# BLE_PP_v15.net
KiCad netlist of a schematic drawn in EAGLE
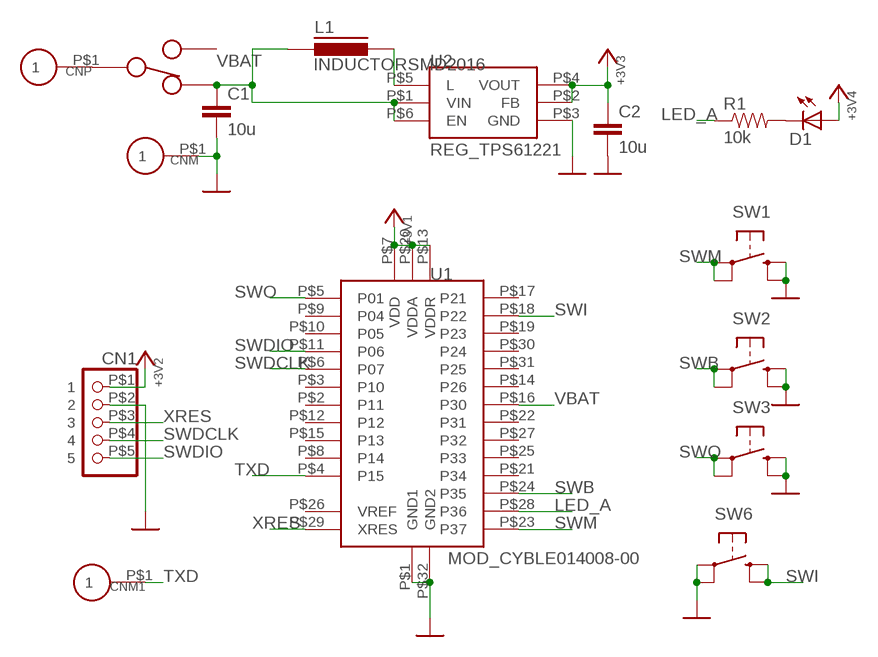
[diagram p0: schematic, sheet 1]

(export (version "E")
  (design (tool "Eeschema 10.0.6"))
  (components
    (comp (ref "C1")
      (value "10u")
      (footprint "eagle-import:0603")
      (libsource (lib "eagle-import") (part "CAP0603"))
    )
    (comp (ref "C2")
      (value "10u")
      (footprint "eagle-import:0603")
      (libsource (lib "eagle-import") (part "CAP0603"))
    )
    (comp (ref "CN1")
      (value "CON_PINHD-1X550MIL")
      (footprint "eagle-import:1X5_50MIL")
      (libsource (lib "eagle-import") (part "CON_PINHD-1X550MIL"))
    )
    (comp (ref "CNM")
      (value "CON_P01SMD1MM")
      (footprint "eagle-import:PAD_SMD1MM")
      (libsource (lib "eagle-import") (part "CON_P01SMD1MM"))
    )
    (comp (ref "CNM1")
      (value "CON_P01SMD1MM")
      (footprint "eagle-import:PAD_SMD1MM")
      (libsource (lib "eagle-import") (part "CON_P01SMD1MM"))
    )
    (comp (ref "CNP")
      (value "CON_P01SMD1MM")
      (footprint "eagle-import:PAD_SMD1MM")
      (libsource (lib "eagle-import") (part "CON_P01SMD1MM"))
    )
    (comp (ref "D1")
      (value "LED0603")
      (footprint "eagle-import:SPARKFUN_LED-0603")
      (libsource (lib "eagle-import") (part "LED0603"))
    )
    (comp (ref "L1")
      (value "INDUCTORSMD2016")
      (footprint "eagle-import:2016")
      (libsource (lib "eagle-import") (part "INDUCTORSMD2016"))
    )
    (comp (ref "R1")
      (value "10k")
      (footprint "eagle-import:0603")
      (libsource (lib "eagle-import") (part "RES0603"))
    )
    (comp (ref "SW1")
      (value "SW_TACTEVQP2")
      (footprint "eagle-import:SW_EVQP2")
      (libsource (lib "eagle-import") (part "SW_TACTEVQP2"))
    )
    (comp (ref "SW2")
      (value "SW_TACTEVQPLNA08NOGND")
      (footprint "eagle-import:SW_EVQPLBA08_NOGND")
      (libsource (lib "eagle-import") (part "SW_TACTEVQPLNA08NOGND"))
    )
    (comp (ref "SW3")
      (value "SW_TACTEVQPLNA08NOGND")
      (footprint "eagle-import:SW_EVQPLBA08_NOGND")
      (libsource (lib "eagle-import") (part "SW_TACTEVQPLNA08NOGND"))
    )
    (comp (ref "SW4")
      (value "SW_SLIDECUS12B")
      (footprint "eagle-import:SW_CUS-12B")
      (libsource (lib "eagle-import") (part "SW_SLIDECUS12B"))
    )
    (comp (ref "SW6")
      (value "SW_TACTEVQP7")
      (footprint "eagle-import:SW_EVQP7")
      (libsource (lib "eagle-import") (part "SW_TACTEVQP7"))
    )
    (comp (ref "U1")
      (value "MOD_CYBLE014008-00")
      (footprint "eagle-import:MOD_CYBLE014008-00")
      (libsource (lib "eagle-import") (part "MOD_CYBLE014008-00"))
    )
    (comp (ref "U2")
      (value "REG_TPS61221")
      (footprint "eagle-import:SC70-6")
      (libsource (lib "eagle-import") (part "REG_TPS61221"))
    )
  )
  (nets
    (net (code "1") (name "/LED_A") (class "Default")
      (node (ref "R1") (pin "1") (pinfunction "1_1") (pintype "passive"))
      (node (ref "U1") (pin "P$28") (pinfunction "P36_P$28") (pintype "bidirectional"))
    )
    (net (code "2") (name "/P$3") (class "Default")
      (node (ref "SW4") (pin "P$3") (pinfunction "P$3_P$3") (pintype "power_in"))
    )
    (net (code "3") (name "/SWB") (class "Default")
      (node (ref "SW2") (pin "A1") (pinfunction "P_A1") (pintype "passive"))
      (node (ref "SW2") (pin "A2") (pinfunction "P1_A2") (pintype "passive"))
      (node (ref "U1") (pin "P$24") (pinfunction "P35_P$24") (pintype "bidirectional"))
    )
    (net (code "4") (name "/SWDCLK") (class "Default")
      (node (ref "CN1") (pin "P$4") (pinfunction "4_P$4") (pintype "passive"))
      (node (ref "U1") (pin "P$6") (pinfunction "P07_P$6") (pintype "bidirectional"))
    )
    (net (code "5") (name "/SWDIO") (class "Default")
      (node (ref "CN1") (pin "P$5") (pinfunction "5_P$5") (pintype "passive"))
      (node (ref "U1") (pin "P$11") (pinfunction "P06_P$11") (pintype "bidirectional"))
    )
    (net (code "6") (name "/SWI") (class "Default")
      (node (ref "SW6") (pin "P$2A") (pinfunction "S_P$2A") (pintype "passive"))
      (node (ref "SW6") (pin "P$2B") (pinfunction "S1_P$2B") (pintype "passive"))
      (node (ref "U1") (pin "P$18") (pinfunction "P22_P$18") (pintype "bidirectional"))
    )
    (net (code "7") (name "/SWM") (class "Default")
      (node (ref "SW1") (pin "PA1") (pinfunction "P_PA1") (pintype "passive"))
      (node (ref "SW1") (pin "PA2") (pinfunction "P1_PA2") (pintype "passive"))
      (node (ref "U1") (pin "P$23") (pinfunction "P37_P$23") (pintype "bidirectional"))
    )
    (net (code "8") (name "/SWO") (class "Default")
      (node (ref "SW3") (pin "A1") (pinfunction "P_A1") (pintype "passive"))
      (node (ref "SW3") (pin "A2") (pinfunction "P1_A2") (pintype "passive"))
      (node (ref "U1") (pin "P$5") (pinfunction "P01_P$5") (pintype "bidirectional"))
    )
    (net (code "9") (name "/TXD") (class "Default")
      (node (ref "CNM1") (pin "P$1") (pinfunction "1_P$1") (pintype "bidirectional"))
      (node (ref "U1") (pin "P$4") (pinfunction "P15_P$4") (pintype "bidirectional"))
    )
    (net (code "10") (name "/VBAT") (class "Default")
      (node (ref "C1") (pin "1") (pinfunction "1_1") (pintype "passive"))
      (node (ref "L1") (pin "P$1") (pinfunction "1_P$1") (pintype "passive"))
      (node (ref "SW4") (pin "P$1") (pinfunction "P$1_P$1") (pintype "power_in"))
      (node (ref "U1") (pin "P$16") (pinfunction "P30_P$16") (pintype "bidirectional"))
      (node (ref "U2") (pin "P$1") (pinfunction "VIN_P$1") (pintype "bidirectional"))
      (node (ref "U2") (pin "P$6") (pinfunction "EN_P$6") (pintype "bidirectional"))
    )
    (net (code "11") (name "/XRES") (class "Default")
      (node (ref "CN1") (pin "P$3") (pinfunction "3_P$3") (pintype "passive"))
      (node (ref "U1") (pin "P$29") (pinfunction "XRES_P$29") (pintype "bidirectional"))
    )
    (net (code "12") (name "Net-(CNP-1)") (class "Default")
      (node (ref "CNP") (pin "P$1") (pinfunction "1_P$1") (pintype "bidirectional"))
      (node (ref "SW4") (pin "P$2") (pinfunction "P$2_P$2") (pintype "power_in"))
    )
    (net (code "13") (name "Net-(D1-PadC)") (class "Default")
      (node (ref "D1") (pin "C") (pinfunction "C_C") (pintype "passive"))
      (node (ref "R1") (pin "2") (pinfunction "2_2") (pintype "passive"))
    )
    (net (code "14") (name "Net-(L1-2)") (class "Default")
      (node (ref "L1") (pin "P$2") (pinfunction "2_P$2") (pintype "passive"))
      (node (ref "U2") (pin "P$5") (pinfunction "L_P$5") (pintype "bidirectional"))
    )
    (net (code "15") (name "POW_+3V3") (class "Default")
      (node (ref "C2") (pin "1") (pinfunction "1_1") (pintype "passive"))
      (node (ref "CN1") (pin "P$1") (pinfunction "1_P$1") (pintype "passive"))
      (node (ref "D1") (pin "A") (pinfunction "A_A") (pintype "passive"))
      (node (ref "U1") (pin "P$13") (pinfunction "VDDR_P$13") (pintype "bidirectional"))
      (node (ref "U1") (pin "P$20") (pinfunction "VDDA_P$20") (pintype "bidirectional"))
      (node (ref "U1") (pin "P$7") (pinfunction "VDD_P$7") (pintype "bidirectional"))
      (node (ref "U2") (pin "P$2") (pinfunction "FB_P$2") (pintype "bidirectional"))
      (node (ref "U2") (pin "P$4") (pinfunction "VOUT_P$4") (pintype "bidirectional"))
    )
    (net (code "16") (name "POW_GND") (class "Default")
      (node (ref "C1") (pin "2") (pinfunction "2_2") (pintype "passive"))
      (node (ref "C2") (pin "2") (pinfunction "2_2") (pintype "passive"))
      (node (ref "CN1") (pin "P$2") (pinfunction "2_P$2") (pintype "passive"))
      (node (ref "CNM") (pin "P$1") (pinfunction "1_P$1") (pintype "bidirectional"))
      (node (ref "SW1") (pin "PB1") (pinfunction "S_PB1") (pintype "passive"))
      (node (ref "SW1") (pin "PB2") (pinfunction "S1_PB2") (pintype "passive"))
      (node (ref "SW2") (pin "B1") (pinfunction "S_B1") (pintype "passive"))
      (node (ref "SW2") (pin "B2") (pinfunction "S1_B2") (pintype "passive"))
      (node (ref "SW3") (pin "B1") (pinfunction "S_B1") (pintype "passive"))
      (node (ref "SW3") (pin "B2") (pinfunction "S1_B2") (pintype "passive"))
      (node (ref "SW6") (pin "P$1A") (pinfunction "P_P$1A") (pintype "passive"))
      (node (ref "SW6") (pin "P$1B") (pinfunction "P1_P$1B") (pintype "passive"))
      (node (ref "U1") (pin "P$1") (pinfunction "GND1_P$1") (pintype "bidirectional"))
      (node (ref "U1") (pin "P$32") (pinfunction "GND2_P$32") (pintype "bidirectional"))
      (node (ref "U2") (pin "P$3") (pinfunction "GND_P$3") (pintype "bidirectional"))
    )
    (net (code "17") (name "unconnected-(U1-P04-PadP$9)") (class "Default")
      (node (ref "U1") (pin "P$9") (pinfunction "P04_P$9") (pintype "bidirectional"))
    )
    (net (code "18") (name "unconnected-(U1-P05-PadP$10)") (class "Default")
      (node (ref "U1") (pin "P$10") (pinfunction "P05_P$10") (pintype "bidirectional"))
    )
    (net (code "19") (name "unconnected-(U1-P10-PadP$3)") (class "Default")
      (node (ref "U1") (pin "P$3") (pinfunction "P10_P$3") (pintype "bidirectional"))
    )
    (net (code "20") (name "unconnected-(U1-P11-PadP$2)") (class "Default")
      (node (ref "U1") (pin "P$2") (pinfunction "P11_P$2") (pintype "bidirectional"))
    )
    (net (code "21") (name "unconnected-(U1-P12-PadP$12)") (class "Default")
      (node (ref "U1") (pin "P$12") (pinfunction "P12_P$12") (pintype "bidirectional"))
    )
    (net (code "22") (name "unconnected-(U1-P13-PadP$15)") (class "Default")
      (node (ref "U1") (pin "P$15") (pinfunction "P13_P$15") (pintype "bidirectional"))
    )
    (net (code "23") (name "unconnected-(U1-P14-PadP$8)") (class "Default")
      (node (ref "U1") (pin "P$8") (pinfunction "P14_P$8") (pintype "bidirectional"))
    )
    (net (code "24") (name "unconnected-(U1-P21-PadP$17)") (class "Default")
      (node (ref "U1") (pin "P$17") (pinfunction "P21_P$17") (pintype "bidirectional"))
    )
    (net (code "25") (name "unconnected-(U1-P23-PadP$19)") (class "Default")
      (node (ref "U1") (pin "P$19") (pinfunction "P23_P$19") (pintype "bidirectional"))
    )
    (net (code "26") (name "unconnected-(U1-P24-PadP$30)") (class "Default")
      (node (ref "U1") (pin "P$30") (pinfunction "P24_P$30") (pintype "bidirectional"))
    )
    (net (code "27") (name "unconnected-(U1-P25-PadP$31)") (class "Default")
      (node (ref "U1") (pin "P$31") (pinfunction "P25_P$31") (pintype "bidirectional"))
    )
    (net (code "28") (name "unconnected-(U1-P26-PadP$14)") (class "Default")
      (node (ref "U1") (pin "P$14") (pinfunction "P26_P$14") (pintype "bidirectional"))
    )
    (net (code "29") (name "unconnected-(U1-P31-PadP$22)") (class "Default")
      (node (ref "U1") (pin "P$22") (pinfunction "P31_P$22") (pintype "bidirectional"))
    )
    (net (code "30") (name "unconnected-(U1-P32-PadP$27)") (class "Default")
      (node (ref "U1") (pin "P$27") (pinfunction "P32_P$27") (pintype "bidirectional"))
    )
    (net (code "31") (name "unconnected-(U1-P33-PadP$25)") (class "Default")
      (node (ref "U1") (pin "P$25") (pinfunction "P33_P$25") (pintype "bidirectional"))
    )
    (net (code "32") (name "unconnected-(U1-P34-PadP$21)") (class "Default")
      (node (ref "U1") (pin "P$21") (pinfunction "P34_P$21") (pintype "bidirectional"))
    )
    (net (code "33") (name "unconnected-(U1-VREF-PadP$26)") (class "Default")
      (node (ref "U1") (pin "P$26") (pinfunction "VREF_P$26") (pintype "bidirectional"))
    )
  )
)
